# MOTOR.net
KiCad netlist of a schematic drawn in Altium Designer
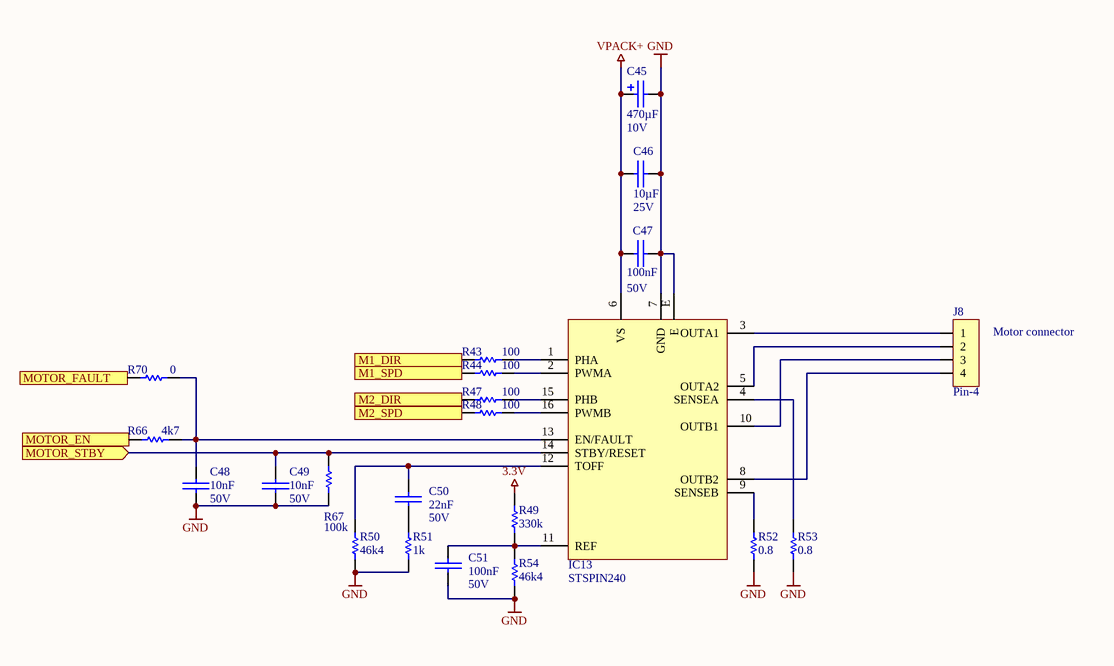
[diagram p0: MOTOR.SchDoc]

(export (version "E")
  (design (tool "Eeschema 10.0.6"))
  (components
    (comp (ref "C45")
      (value "470µF")
      (footprint "CD6.3H12TH")
      (description "CAP ALUM 470UF 20% 10V TH")
      (fields
        (field (name "MANUFACTURER") "AISHI(Aihua Group)")
        (field (name "TOLERANCE") "20%")
        (field (name "VOLTAGE") "10V")
      )
      (libsource (lib "bond-altium-excell") (part "cap-pol"))
    )
    (comp (ref "C46")
      (value "10µF")
      (footprint "C0603")
      (description "CAP CER 10UF 25V X5R 10% SMD")
      (fields
        (field (name "MANUFACTURER") "Murata Electronics")
        (field (name "TOLERANCE") "10%")
        (field (name "VOLTAGE") "25V")
      )
      (libsource (lib "bond-altium-excell") (part "cap_non_pol"))
    )
    (comp (ref "C47")
      (value "100nF")
      (footprint "C0402")
      (description "CAP CER 0.1UF 50V X5R 0402")
      (fields
        (field (name "MANUFACTURER") "Murata Electronics")
        (field (name "TOLERANCE") "5%")
        (field (name "VOLTAGE") "50V")
      )
      (libsource (lib "bond-altium-excell") (part "cap_non_pol"))
    )
    (comp (ref "C48")
      (value "10nF")
      (footprint "C0402")
      (description "CAP CER 10000PF 50V X7R 0402")
      (fields
        (field (name "MANUFACTURER") "Samsung Electro-Mechanics")
        (field (name "TOLERANCE") "10%")
        (field (name "VOLTAGE") "50V")
      )
      (libsource (lib "bond-altium-excell") (part "cap_non_pol"))
    )
    (comp (ref "C49")
      (value "10nF")
      (footprint "C0402")
      (description "CAP CER 10000PF 50V X7R 0402")
      (fields
        (field (name "MANUFACTURER") "Samsung Electro-Mechanics")
        (field (name "TOLERANCE") "10%")
        (field (name "VOLTAGE") "50V")
      )
      (libsource (lib "bond-altium-excell") (part "cap_non_pol"))
    )
    (comp (ref "C50")
      (value "22nF")
      (footprint "C0402")
      (description "CAP CER 0.022UF 50V X7R 0402")
      (fields
        (field (name "MANUFACTURER") "Murata Electronics")
        (field (name "TOLERANCE") "10%")
        (field (name "VOLTAGE") "50V")
      )
      (libsource (lib "bond-altium-excell") (part "cap_non_pol"))
    )
    (comp (ref "C51")
      (value "100nF")
      (footprint "TH5.08")
      (description "CAP CER TH 100nF X7R 50V")
      (fields
        (field (name "MANUFACTURER") "FH")
        (field (name "TOLERANCE") "10%")
        (field (name "VOLTAGE") "50V")
      )
      (libsource (lib "bond-altium-excell") (part "cap_non_pol"))
    )
    (comp (ref "IC13")
      (value "STSPIN240")
      (footprint "VFQFPN-16")
      (description "IC HALF BRIDGE DRV 1.3A 16VFQFPN")
      (fields (field (name "MANUFACTURER") "STMicroelectronics"))
      (libsource (lib "bond-altium-excell") (part "STSPIN240"))
    )
    (comp (ref "J8")
      (value "Pin-4")
      (footprint "110990030")
      (description "GROVE 2MM 4PIN VERT CONN 10PCS")
      (fields (field (name "MANUFACTURER") "Seeed Technology Co., Ltd"))
      (libsource (lib "bond-altium-excell") (part "Pin-4"))
    )
    (comp (ref "R43")
      (value "100")
      (footprint "R0402")
      (description "RES SMD 100 OHM 1% 1/5W 0402")
      (fields (field (name "MANUFACTURER") "Vishay Dale") (field (name "TOLERANCE") "1%"))
      (libsource (lib "bond-altium-excell") (part "resistor"))
    )
    (comp (ref "R44")
      (value "100")
      (footprint "R0402")
      (description "RES SMD 100 OHM 1% 1/5W 0402")
      (fields (field (name "MANUFACTURER") "Vishay Dale") (field (name "TOLERANCE") "1%"))
      (libsource (lib "bond-altium-excell") (part "resistor"))
    )
    (comp (ref "R47")
      (value "100")
      (footprint "R0402")
      (description "RES SMD 100 OHM 1% 1/5W 0402")
      (fields (field (name "MANUFACTURER") "Vishay Dale") (field (name "TOLERANCE") "1%"))
      (libsource (lib "bond-altium-excell") (part "resistor"))
    )
    (comp (ref "R48")
      (value "100")
      (footprint "R0402")
      (description "RES SMD 100 OHM 1% 1/5W 0402")
      (fields (field (name "MANUFACTURER") "Vishay Dale") (field (name "TOLERANCE") "1%"))
      (libsource (lib "bond-altium-excell") (part "resistor"))
    )
    (comp (ref "R49")
      (value "330k")
      (footprint "R0402")
      (description "RES 330K OHM 1% 1/16W 0402")
      (fields (field (name "MANUFACTURER") "YAGEO") (field (name "TOLERANCE") "1%"))
      (libsource (lib "bond-altium-excell") (part "resistor"))
    )
    (comp (ref "R50")
      (value "46k4")
      (footprint "R0402")
      (description "RES SMD 46.4K OHM 1% 1/16W 0402")
      (fields (field (name "MANUFACTURER") "Yageo") (field (name "TOLERANCE") "1%"))
      (libsource (lib "bond-altium-excell") (part "resistor"))
    )
    (comp (ref "R51")
      (value "1k")
      (footprint "R0402")
      (description "RES SMD 1K OHM 1% 1/10W 0402")
      (fields (field (name "MANUFACTURER") "Panasonic Electronic Components") (field (name "TOLERANCE") "1%"))
      (libsource (lib "bond-altium-excell") (part "resistor"))
    )
    (comp (ref "R52")
      (value "0.8")
      (footprint "R1206")
      (description "RES 0.002 OHM 1% 1W 1206")
      (fields (field (name "MANUFACTURER") "Thin Film Technology Corp.") (field (name "TOLERANCE") "1%"))
      (libsource (lib "bond-altium-excell") (part "resistor"))
    )
    (comp (ref "R53")
      (value "0.8")
      (footprint "R1206")
      (description "RES 0.002 OHM 1% 1W 1206")
      (fields (field (name "MANUFACTURER") "Thin Film Technology Corp.") (field (name "TOLERANCE") "1%"))
      (libsource (lib "bond-altium-excell") (part "resistor"))
    )
    (comp (ref "R54")
      (value "46k4")
      (footprint "R0402")
      (description "RES SMD 46.4K OHM 1% 1/16W 0402")
      (fields (field (name "MANUFACTURER") "Yageo") (field (name "TOLERANCE") "1%"))
      (libsource (lib "bond-altium-excell") (part "resistor"))
    )
    (comp (ref "R66")
      (value "4k7")
      (footprint "R0402")
      (description "RES SMD 4.7K OHM 1% 1/10W 0402")
      (fields (field (name "MANUFACTURER") "Panasonic Electronic Components") (field (name "TOLERANCE") "1%"))
      (libsource (lib "bond-altium-excell") (part "resistor"))
    )
    (comp (ref "R67")
      (value "100k")
      (footprint "R0402")
      (description "RES SMD 100K OHM 1% 1/10W 0402")
      (fields (field (name "MANUFACTURER") "Panasonic Electronic Components") (field (name "TOLERANCE") "1%"))
      (libsource (lib "bond-altium-excell") (part "resistor"))
    )
    (comp (ref "R70")
      (value "0")
      (footprint "R0402")
      (description "RES SMD 0 OHM JUMPER 1/10W 0402")
      (fields (field (name "MANUFACTURER") "Panasonic Electronic Components") (field (name "TOLERANCE") "1%"))
      (libsource (lib "bond-altium-excell") (part "resistor"))
    )
  )
  (nets
    (net (code "1") (name "/M1_DIR") (class "Default")
      (node (ref "R43") (pin "2") (pinfunction "2_2") (pintype "passive"))
    )
    (net (code "2") (name "/M1_SPD") (class "Default")
      (node (ref "R44") (pin "2") (pinfunction "2_2") (pintype "passive"))
    )
    (net (code "3") (name "/M2_DIR") (class "Default")
      (node (ref "R47") (pin "2") (pinfunction "2_2") (pintype "passive"))
    )
    (net (code "4") (name "/M2_SPD") (class "Default")
      (node (ref "R48") (pin "2") (pinfunction "2_2") (pintype "passive"))
    )
    (net (code "5") (name "/MOTOR_EN") (class "Default")
      (node (ref "R66") (pin "2") (pinfunction "2_2") (pintype "passive"))
    )
    (net (code "6") (name "/MOTOR_FAULT") (class "Default")
      (node (ref "R70") (pin "2") (pinfunction "2_2") (pintype "passive"))
    )
    (net (code "7") (name "/MOTOR_STBY") (class "Default")
      (node (ref "C49") (pin "1") (pinfunction "1_1") (pintype "passive"))
      (node (ref "IC13") (pin "14") (pinfunction "STBY/RESET_14") (pintype "passive"))
      (node (ref "R67") (pin "1") (pinfunction "1_1") (pintype "passive"))
    )
    (net (code "8") (name "3.3V") (class "Default")
      (node (ref "R49") (pin "1") (pinfunction "1_1") (pintype "passive"))
    )
    (net (code "9") (name "GND") (class "Default")
      (node (ref "C45") (pin "-") (pinfunction "-_-") (pintype "passive"))
      (node (ref "C46") (pin "2") (pinfunction "2_2") (pintype "passive"))
      (node (ref "C47") (pin "1") (pinfunction "1_1") (pintype "passive"))
      (node (ref "C48") (pin "2") (pinfunction "2_2") (pintype "passive"))
      (node (ref "C49") (pin "2") (pinfunction "2_2") (pintype "passive"))
      (node (ref "C51") (pin "1") (pinfunction "1_1") (pintype "passive"))
      (node (ref "IC13") (pin "7") (pinfunction "GND_7") (pintype "passive"))
      (node (ref "IC13") (pin "E") (pinfunction "E_E") (pintype "passive"))
      (node (ref "R50") (pin "2") (pinfunction "2_2") (pintype "passive"))
      (node (ref "R51") (pin "1") (pinfunction "1_1") (pintype "passive"))
      (node (ref "R52") (pin "1") (pinfunction "1_1") (pintype "passive"))
      (node (ref "R53") (pin "1") (pinfunction "1_1") (pintype "passive"))
      (node (ref "R54") (pin "2") (pinfunction "2_2") (pintype "passive"))
      (node (ref "R67") (pin "2") (pinfunction "2_2") (pintype "passive"))
    )
    (net (code "10") (name "Net-(C50-Pad1)") (class "Default")
      (node (ref "C50") (pin "1") (pinfunction "1_1") (pintype "passive"))
      (node (ref "R51") (pin "2") (pinfunction "2_2") (pintype "passive"))
    )
    (net (code "11") (name "Net-(IC13-EN{slash}FAULT)") (class "Default")
      (node (ref "C48") (pin "1") (pinfunction "1_1") (pintype "passive"))
      (node (ref "IC13") (pin "13") (pinfunction "EN/FAULT_13") (pintype "passive"))
      (node (ref "R66") (pin "1") (pinfunction "1_1") (pintype "passive"))
      (node (ref "R70") (pin "1") (pinfunction "1_1") (pintype "passive"))
    )
    (net (code "12") (name "Net-(IC13-OUTA1)") (class "Default")
      (node (ref "IC13") (pin "3") (pinfunction "OUTA1_3") (pintype "passive"))
      (node (ref "J8") (pin "1") (pinfunction "1_1") (pintype "passive"))
    )
    (net (code "13") (name "Net-(IC13-OUTA2)") (class "Default")
      (node (ref "IC13") (pin "5") (pinfunction "OUTA2_5") (pintype "passive"))
      (node (ref "J8") (pin "2") (pinfunction "2_2") (pintype "passive"))
    )
    (net (code "14") (name "Net-(IC13-OUTB1)") (class "Default")
      (node (ref "IC13") (pin "10") (pinfunction "OUTB1_10") (pintype "passive"))
      (node (ref "J8") (pin "3") (pinfunction "3_3") (pintype "passive"))
    )
    (net (code "15") (name "Net-(IC13-OUTB2)") (class "Default")
      (node (ref "IC13") (pin "8") (pinfunction "OUTB2_8") (pintype "passive"))
      (node (ref "J8") (pin "4") (pinfunction "4_4") (pintype "passive"))
    )
    (net (code "16") (name "Net-(IC13-PHA)") (class "Default")
      (node (ref "IC13") (pin "1") (pinfunction "PHA_1") (pintype "passive"))
      (node (ref "R43") (pin "1") (pinfunction "1_1") (pintype "passive"))
    )
    (net (code "17") (name "Net-(IC13-PHB)") (class "Default")
      (node (ref "IC13") (pin "15") (pinfunction "PHB_15") (pintype "passive"))
      (node (ref "R47") (pin "1") (pinfunction "1_1") (pintype "passive"))
    )
    (net (code "18") (name "Net-(IC13-PWMA)") (class "Default")
      (node (ref "IC13") (pin "2") (pinfunction "PWMA_2") (pintype "passive"))
      (node (ref "R44") (pin "1") (pinfunction "1_1") (pintype "passive"))
    )
    (net (code "19") (name "Net-(IC13-PWMB)") (class "Default")
      (node (ref "IC13") (pin "16") (pinfunction "PWMB_16") (pintype "passive"))
      (node (ref "R48") (pin "1") (pinfunction "1_1") (pintype "passive"))
    )
    (net (code "20") (name "Net-(IC13-REF)") (class "Default")
      (node (ref "C51") (pin "2") (pinfunction "2_2") (pintype "passive"))
      (node (ref "IC13") (pin "11") (pinfunction "REF_11") (pintype "passive"))
      (node (ref "R49") (pin "2") (pinfunction "2_2") (pintype "passive"))
      (node (ref "R54") (pin "1") (pinfunction "1_1") (pintype "passive"))
    )
    (net (code "21") (name "Net-(IC13-SENSEA)") (class "Default")
      (node (ref "IC13") (pin "4") (pinfunction "SENSEA_4") (pintype "passive"))
      (node (ref "R53") (pin "2") (pinfunction "2_2") (pintype "passive"))
    )
    (net (code "22") (name "Net-(IC13-SENSEB)") (class "Default")
      (node (ref "IC13") (pin "9") (pinfunction "SENSEB_9") (pintype "passive"))
      (node (ref "R52") (pin "2") (pinfunction "2_2") (pintype "passive"))
    )
    (net (code "23") (name "Net-(IC13-TOFF)") (class "Default")
      (node (ref "C50") (pin "2") (pinfunction "2_2") (pintype "passive"))
      (node (ref "IC13") (pin "12") (pinfunction "TOFF_12") (pintype "passive"))
      (node (ref "R50") (pin "1") (pinfunction "1_1") (pintype "passive"))
    )
    (net (code "24") (name "VPACK+") (class "Default")
      (node (ref "C45") (pin "+") (pinfunction "+_+") (pintype "passive"))
      (node (ref "C46") (pin "1") (pinfunction "1_1") (pintype "passive"))
      (node (ref "C47") (pin "2") (pinfunction "2_2") (pintype "passive"))
      (node (ref "IC13") (pin "6") (pinfunction "VS_6") (pintype "passive"))
    )
  )
)
